# 7_seg.net
KiCad netlist of a schematic drawn in EAGLE
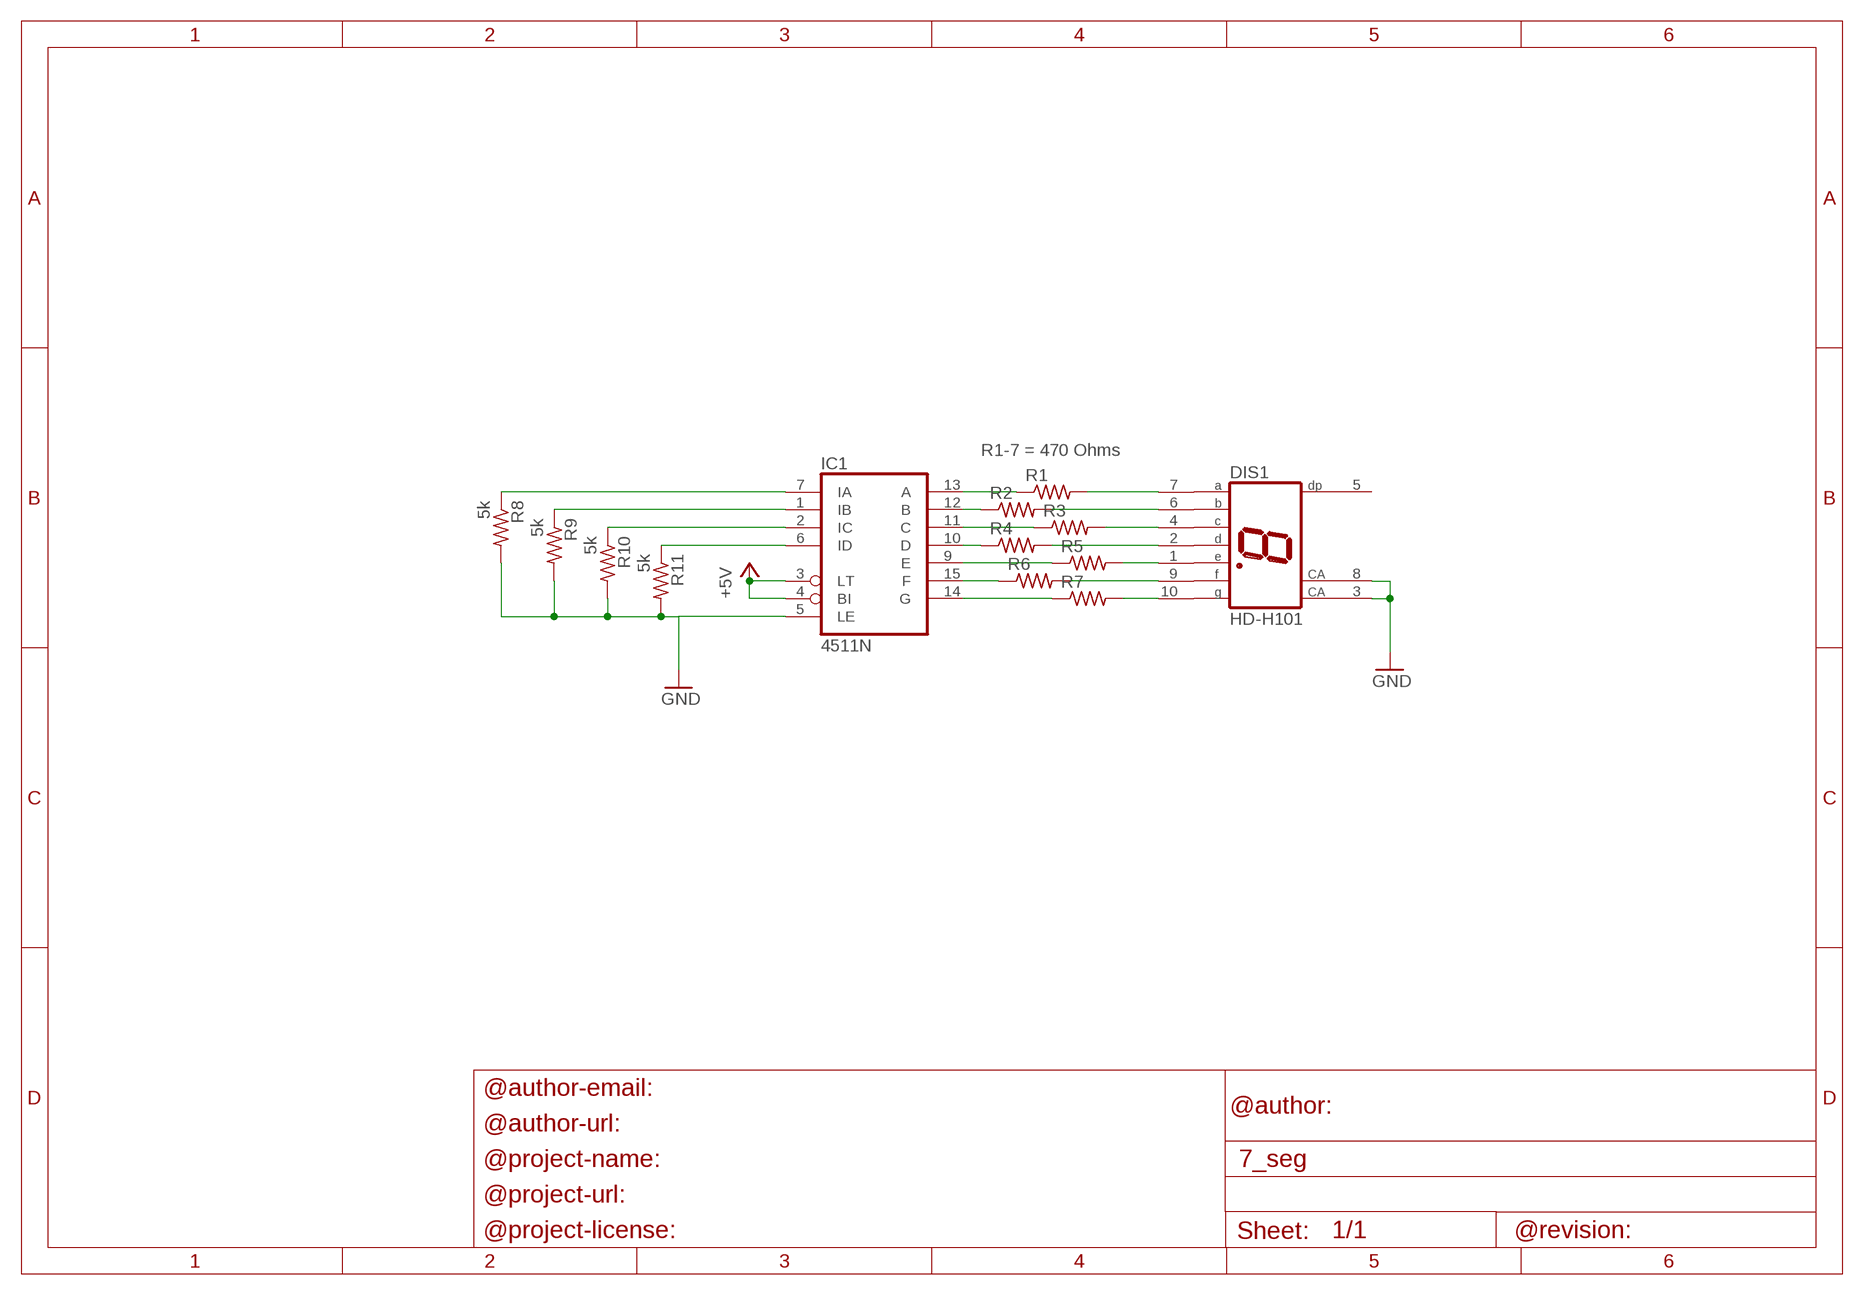
[diagram p0: schematic, sheet 1]

(export (version "E")
  (design (tool "Eeschema 10.0.6"))
  (components
    (comp (ref "DIS1")
      (value "HD-H101")
      (footprint "eagle-import:HDSP-M")
      (libsource (lib "eagle-import") (part "HD-H101"))
    )
    (comp (ref "IC1")
      (value "4511N")
      (footprint "eagle-import:DIL16")
      (libsource (lib "eagle-import") (part "4511N"))
    )
    (comp (ref "R1")
      (value "R-US_0204/7")
      (footprint "eagle-import:0204_7")
      (libsource (lib "eagle-import") (part "R-US_0204/7"))
    )
    (comp (ref "R2")
      (value "R-US_0204/7")
      (footprint "eagle-import:0204_7")
      (libsource (lib "eagle-import") (part "R-US_0204/7"))
    )
    (comp (ref "R3")
      (value "R-US_0204/7")
      (footprint "eagle-import:0204_7")
      (libsource (lib "eagle-import") (part "R-US_0204/7"))
    )
    (comp (ref "R4")
      (value "R-US_0204/7")
      (footprint "eagle-import:0204_7")
      (libsource (lib "eagle-import") (part "R-US_0204/7"))
    )
    (comp (ref "R5")
      (value "R-US_0204/7")
      (footprint "eagle-import:0204_7")
      (libsource (lib "eagle-import") (part "R-US_0204/7"))
    )
    (comp (ref "R6")
      (value "R-US_0204/7")
      (footprint "eagle-import:0204_7")
      (libsource (lib "eagle-import") (part "R-US_0204/7"))
    )
    (comp (ref "R7")
      (value "R-US_0204/7")
      (footprint "eagle-import:0204_7")
      (libsource (lib "eagle-import") (part "R-US_0204/7"))
    )
    (comp (ref "R8")
      (value "5k")
      (footprint "eagle-import:0204_7")
      (libsource (lib "eagle-import") (part "R-US_0204/7"))
    )
    (comp (ref "R9")
      (value "5k")
      (footprint "eagle-import:0204_7")
      (libsource (lib "eagle-import") (part "R-US_0204/7"))
    )
    (comp (ref "R10")
      (value "5k")
      (footprint "eagle-import:0204_7")
      (libsource (lib "eagle-import") (part "R-US_0204/7"))
    )
    (comp (ref "R11")
      (value "5k")
      (footprint "eagle-import:0204_7")
      (libsource (lib "eagle-import") (part "R-US_0204/7"))
    )
  )
  (nets
    (net (code "1") (name "+5V") (class "Default")
      (node (ref "IC1") (pin "3") (pinfunction "LT_3") (pintype "input"))
      (node (ref "IC1") (pin "4") (pinfunction "BI_4") (pintype "input"))
    )
    (net (code "2") (name "GND") (class "Default")
      (node (ref "DIS1") (pin "3") (pinfunction "CA_3") (pintype "passive"))
      (node (ref "DIS1") (pin "8") (pinfunction "CA_8") (pintype "passive"))
      (node (ref "IC1") (pin "5") (pinfunction "LE_5") (pintype "input"))
      (node (ref "R10") (pin "2") (pinfunction "2_2") (pintype "passive"))
      (node (ref "R11") (pin "2") (pinfunction "2_2") (pintype "passive"))
      (node (ref "R8") (pin "2") (pinfunction "2_2") (pintype "passive"))
      (node (ref "R9") (pin "2") (pinfunction "2_2") (pintype "passive"))
    )
    (net (code "3") (name "Net-(DIS1-A)") (class "Default")
      (node (ref "DIS1") (pin "7") (pinfunction "A_7") (pintype "passive"))
      (node (ref "R1") (pin "2") (pinfunction "2_2") (pintype "passive"))
    )
    (net (code "4") (name "Net-(DIS1-B)") (class "Default")
      (node (ref "DIS1") (pin "6") (pinfunction "B_6") (pintype "passive"))
      (node (ref "R2") (pin "2") (pinfunction "2_2") (pintype "passive"))
    )
    (net (code "5") (name "Net-(DIS1-C)") (class "Default")
      (node (ref "DIS1") (pin "4") (pinfunction "C_4") (pintype "passive"))
      (node (ref "R3") (pin "2") (pinfunction "2_2") (pintype "passive"))
    )
    (net (code "6") (name "Net-(DIS1-D)") (class "Default")
      (node (ref "DIS1") (pin "2") (pinfunction "D_2") (pintype "passive"))
      (node (ref "R4") (pin "2") (pinfunction "2_2") (pintype "passive"))
    )
    (net (code "7") (name "Net-(DIS1-E)") (class "Default")
      (node (ref "DIS1") (pin "1") (pinfunction "E_1") (pintype "passive"))
      (node (ref "R5") (pin "2") (pinfunction "2_2") (pintype "passive"))
    )
    (net (code "8") (name "Net-(DIS1-F)") (class "Default")
      (node (ref "DIS1") (pin "9") (pinfunction "F_9") (pintype "passive"))
      (node (ref "R6") (pin "2") (pinfunction "2_2") (pintype "passive"))
    )
    (net (code "9") (name "Net-(DIS1-G)") (class "Default")
      (node (ref "DIS1") (pin "10") (pinfunction "G_10") (pintype "passive"))
      (node (ref "R7") (pin "2") (pinfunction "2_2") (pintype "passive"))
    )
    (net (code "10") (name "Net-(IC1A-A)") (class "Default")
      (node (ref "IC1") (pin "13") (pinfunction "A_13") (pintype "output"))
      (node (ref "R1") (pin "1") (pinfunction "1_1") (pintype "passive"))
    )
    (net (code "11") (name "Net-(IC1A-B)") (class "Default")
      (node (ref "IC1") (pin "12") (pinfunction "B_12") (pintype "output"))
      (node (ref "R2") (pin "1") (pinfunction "1_1") (pintype "passive"))
    )
    (net (code "12") (name "Net-(IC1A-C)") (class "Default")
      (node (ref "IC1") (pin "11") (pinfunction "C_11") (pintype "output"))
      (node (ref "R3") (pin "1") (pinfunction "1_1") (pintype "passive"))
    )
    (net (code "13") (name "Net-(IC1A-D)") (class "Default")
      (node (ref "IC1") (pin "10") (pinfunction "D_10") (pintype "output"))
      (node (ref "R4") (pin "1") (pinfunction "1_1") (pintype "passive"))
    )
    (net (code "14") (name "Net-(IC1A-E)") (class "Default")
      (node (ref "IC1") (pin "9") (pinfunction "E_9") (pintype "output"))
      (node (ref "R5") (pin "1") (pinfunction "1_1") (pintype "passive"))
    )
    (net (code "15") (name "Net-(IC1A-F)") (class "Default")
      (node (ref "IC1") (pin "15") (pinfunction "F_15") (pintype "output"))
      (node (ref "R6") (pin "1") (pinfunction "1_1") (pintype "passive"))
    )
    (net (code "16") (name "Net-(IC1A-G)") (class "Default")
      (node (ref "IC1") (pin "14") (pinfunction "G_14") (pintype "output"))
      (node (ref "R7") (pin "1") (pinfunction "1_1") (pintype "passive"))
    )
    (net (code "17") (name "Net-(IC1A-IA)") (class "Default")
      (node (ref "IC1") (pin "7") (pinfunction "IA_7") (pintype "input"))
      (node (ref "R8") (pin "1") (pinfunction "1_1") (pintype "passive"))
    )
    (net (code "18") (name "Net-(IC1A-IB)") (class "Default")
      (node (ref "IC1") (pin "1") (pinfunction "IB_1") (pintype "input"))
      (node (ref "R9") (pin "1") (pinfunction "1_1") (pintype "passive"))
    )
    (net (code "19") (name "Net-(IC1A-IC)") (class "Default")
      (node (ref "IC1") (pin "2") (pinfunction "IC_2") (pintype "input"))
      (node (ref "R10") (pin "1") (pinfunction "1_1") (pintype "passive"))
    )
    (net (code "20") (name "Net-(IC1A-ID)") (class "Default")
      (node (ref "IC1") (pin "6") (pinfunction "ID_6") (pintype "input"))
      (node (ref "R11") (pin "1") (pinfunction "1_1") (pintype "passive"))
    )
    (net (code "21") (name "unconnected-(DIS1-DP-Pad5)") (class "Default")
      (node (ref "DIS1") (pin "5") (pinfunction "DP_5") (pintype "passive"))
    )
  )
)
